# R205D.net
KiCad netlist of a schematic drawn in EAGLE
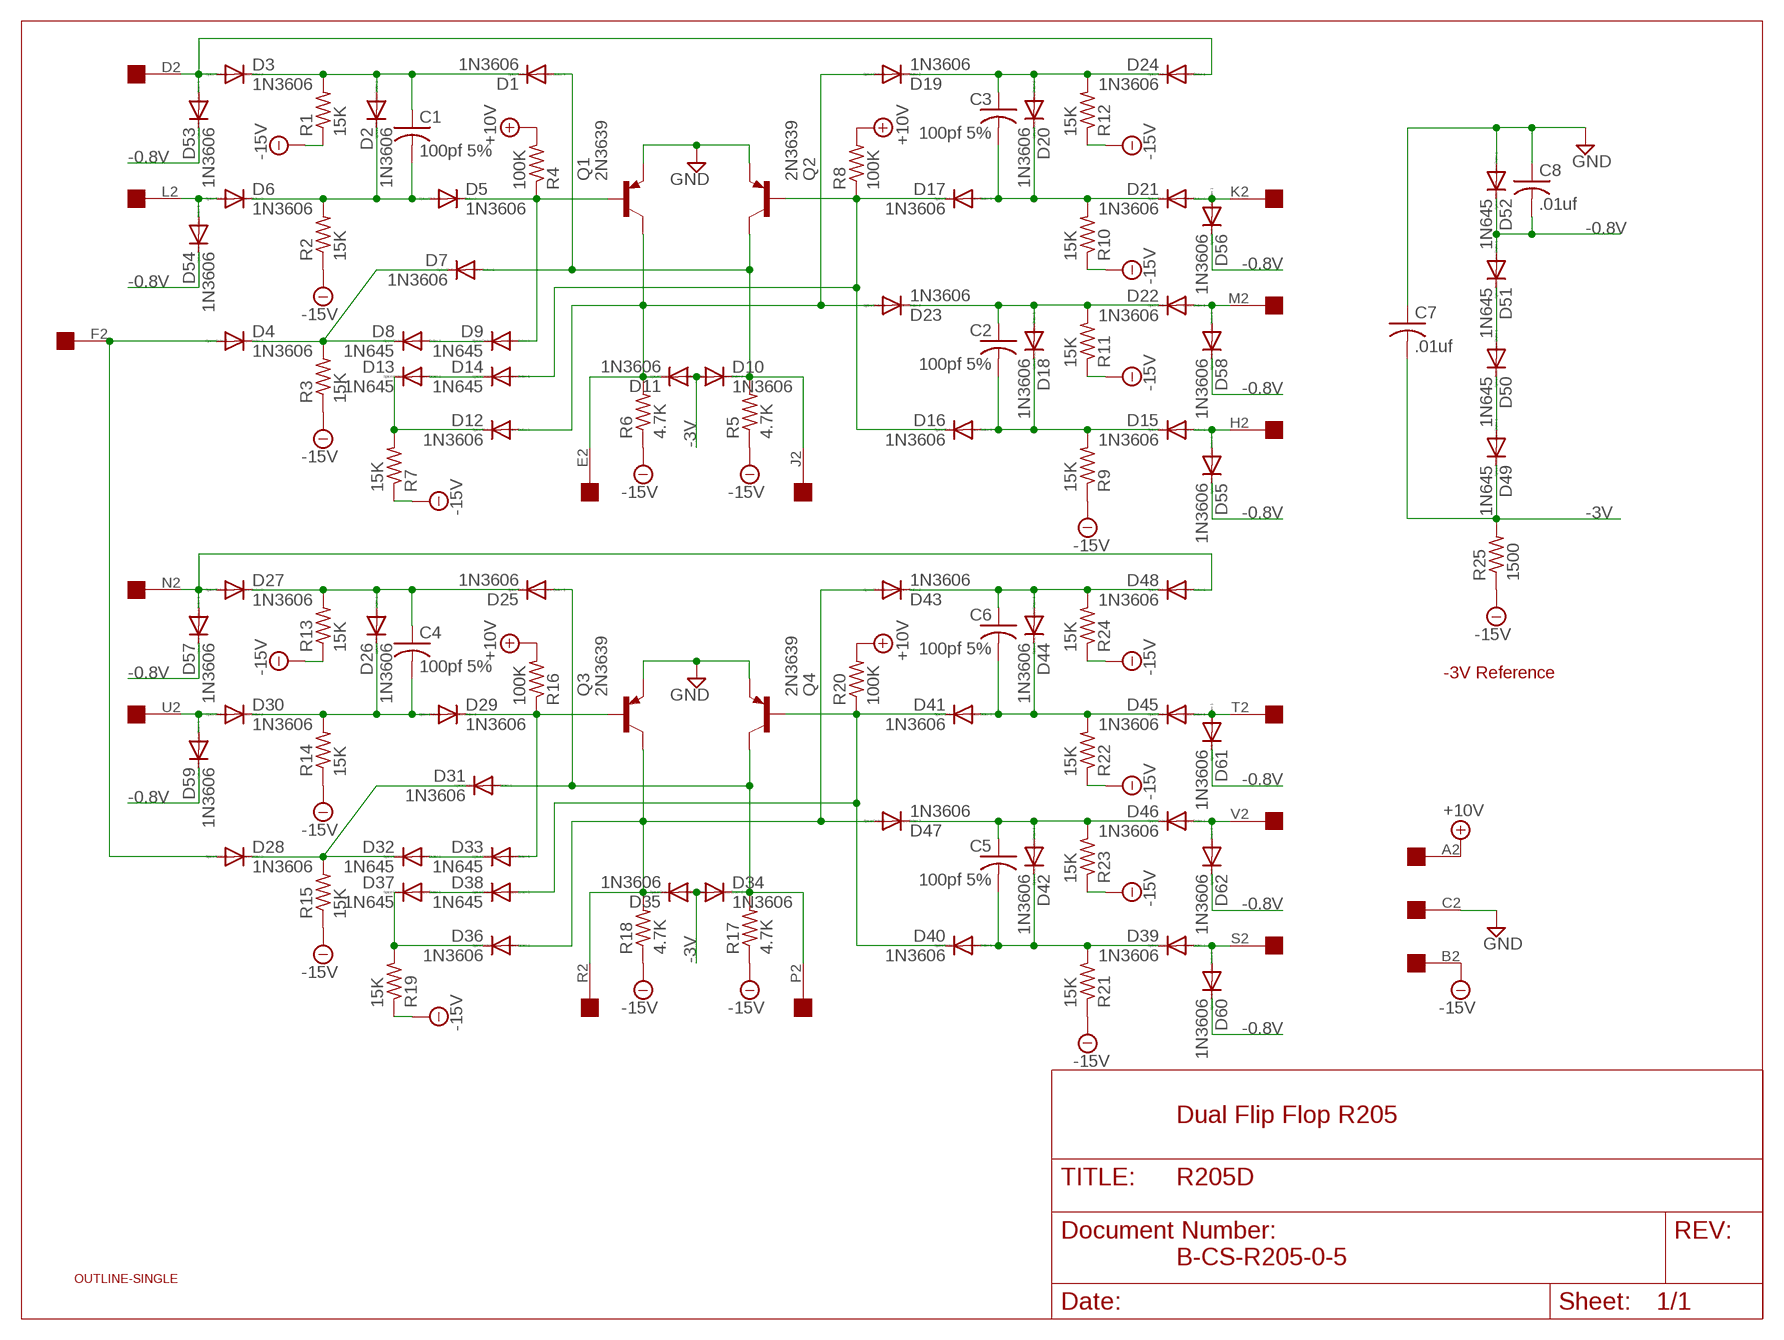
[diagram p0: schematic, sheet 1]

(export (version "E")
  (design (tool "Eeschema 10.0.6"))
  (components
    (comp (ref "C1")
      (value "100pf 5%")
      (footprint "eagle-import:C050-025X075")
      (libsource (lib "eagle-import") (part "C-US050-025X075"))
    )
    (comp (ref "C2")
      (value "100pf 5%")
      (footprint "eagle-import:C050-025X075")
      (libsource (lib "eagle-import") (part "C-US050-025X075"))
    )
    (comp (ref "C3")
      (value "100pf 5%")
      (footprint "eagle-import:C050-025X075")
      (libsource (lib "eagle-import") (part "C-US050-025X075"))
    )
    (comp (ref "C4")
      (value "100pf 5%")
      (footprint "eagle-import:C050-025X075")
      (libsource (lib "eagle-import") (part "C-US050-025X075"))
    )
    (comp (ref "C5")
      (value "100pf 5%")
      (footprint "eagle-import:C050-025X075")
      (libsource (lib "eagle-import") (part "C-US050-025X075"))
    )
    (comp (ref "C6")
      (value "100pf 5%")
      (footprint "eagle-import:C050-025X075")
      (libsource (lib "eagle-import") (part "C-US050-025X075"))
    )
    (comp (ref "C7")
      (value ".01uf")
      (footprint "eagle-import:C050-025X075")
      (libsource (lib "eagle-import") (part "C-US050-025X075"))
    )
    (comp (ref "C8")
      (value ".01uf")
      (footprint "eagle-import:C050-025X075")
      (libsource (lib "eagle-import") (part "C-US050-025X075"))
    )
    (comp (ref "D1")
      (value "1N3606")
      (footprint "eagle-import:DO35-10")
      (libsource (lib "eagle-import") (part "1N4148DO35-10"))
    )
    (comp (ref "D2")
      (value "1N3606")
      (footprint "eagle-import:DO35-10")
      (libsource (lib "eagle-import") (part "1N4148DO35-10"))
    )
    (comp (ref "D3")
      (value "1N3606")
      (footprint "eagle-import:DO35-10")
      (libsource (lib "eagle-import") (part "1N4148DO35-10"))
    )
    (comp (ref "D4")
      (value "1N3606")
      (footprint "eagle-import:DO35-10")
      (libsource (lib "eagle-import") (part "1N4148DO35-10"))
    )
    (comp (ref "D5")
      (value "1N3606")
      (footprint "eagle-import:DO35-10")
      (libsource (lib "eagle-import") (part "1N4148DO35-10"))
    )
    (comp (ref "D6")
      (value "1N3606")
      (footprint "eagle-import:DO35-10")
      (libsource (lib "eagle-import") (part "1N4148DO35-10"))
    )
    (comp (ref "D7")
      (value "1N3606")
      (footprint "eagle-import:DO35-10")
      (libsource (lib "eagle-import") (part "1N4148DO35-10"))
    )
    (comp (ref "D8")
      (value "1N645")
      (footprint "eagle-import:DO35-10")
      (libsource (lib "eagle-import") (part "1N4148DO35-10"))
    )
    (comp (ref "D9")
      (value "1N645")
      (footprint "eagle-import:DO35-10")
      (libsource (lib "eagle-import") (part "1N4148DO35-10"))
    )
    (comp (ref "D10")
      (value "1N3606")
      (footprint "eagle-import:DO35-10")
      (libsource (lib "eagle-import") (part "1N4148DO35-10"))
    )
    (comp (ref "D11")
      (value "1N3606")
      (footprint "eagle-import:DO35-10")
      (libsource (lib "eagle-import") (part "1N4148DO35-10"))
    )
    (comp (ref "D12")
      (value "1N3606")
      (footprint "eagle-import:DO35-10")
      (libsource (lib "eagle-import") (part "1N4148DO35-10"))
    )
    (comp (ref "D13")
      (value "1N645")
      (footprint "eagle-import:DO35-10")
      (libsource (lib "eagle-import") (part "1N4148DO35-10"))
    )
    (comp (ref "D14")
      (value "1N645")
      (footprint "eagle-import:DO35-10")
      (libsource (lib "eagle-import") (part "1N4148DO35-10"))
    )
    (comp (ref "D15")
      (value "1N3606")
      (footprint "eagle-import:DO35-10")
      (libsource (lib "eagle-import") (part "1N4148DO35-10"))
    )
    (comp (ref "D16")
      (value "1N3606")
      (footprint "eagle-import:DO35-10")
      (libsource (lib "eagle-import") (part "1N4148DO35-10"))
    )
    (comp (ref "D17")
      (value "1N3606")
      (footprint "eagle-import:DO35-10")
      (libsource (lib "eagle-import") (part "1N4148DO35-10"))
    )
    (comp (ref "D18")
      (value "1N3606")
      (footprint "eagle-import:DO35-10")
      (libsource (lib "eagle-import") (part "1N4148DO35-10"))
    )
    (comp (ref "D19")
      (value "1N3606")
      (footprint "eagle-import:DO35-10")
      (libsource (lib "eagle-import") (part "1N4148DO35-10"))
    )
    (comp (ref "D20")
      (value "1N3606")
      (footprint "eagle-import:DO35-10")
      (libsource (lib "eagle-import") (part "1N4148DO35-10"))
    )
    (comp (ref "D21")
      (value "1N3606")
      (footprint "eagle-import:DO35-10")
      (libsource (lib "eagle-import") (part "1N4148DO35-10"))
    )
    (comp (ref "D22")
      (value "1N3606")
      (footprint "eagle-import:DO35-10")
      (libsource (lib "eagle-import") (part "1N4148DO35-10"))
    )
    (comp (ref "D23")
      (value "1N3606")
      (footprint "eagle-import:DO35-10")
      (libsource (lib "eagle-import") (part "1N4148DO35-10"))
    )
    (comp (ref "D24")
      (value "1N3606")
      (footprint "eagle-import:DO35-10")
      (libsource (lib "eagle-import") (part "1N4148DO35-10"))
    )
    (comp (ref "D25")
      (value "1N3606")
      (footprint "eagle-import:DO35-10")
      (libsource (lib "eagle-import") (part "1N4148DO35-10"))
    )
    (comp (ref "D26")
      (value "1N3606")
      (footprint "eagle-import:DO35-10")
      (libsource (lib "eagle-import") (part "1N4148DO35-10"))
    )
    (comp (ref "D27")
      (value "1N3606")
      (footprint "eagle-import:DO35-10")
      (libsource (lib "eagle-import") (part "1N4148DO35-10"))
    )
    (comp (ref "D28")
      (value "1N3606")
      (footprint "eagle-import:DO35-10")
      (libsource (lib "eagle-import") (part "1N4148DO35-10"))
    )
    (comp (ref "D29")
      (value "1N3606")
      (footprint "eagle-import:DO35-10")
      (libsource (lib "eagle-import") (part "1N4148DO35-10"))
    )
    (comp (ref "D30")
      (value "1N3606")
      (footprint "eagle-import:DO35-10")
      (libsource (lib "eagle-import") (part "1N4148DO35-10"))
    )
    (comp (ref "D31")
      (value "1N3606")
      (footprint "eagle-import:DO35-10")
      (libsource (lib "eagle-import") (part "1N4148DO35-10"))
    )
    (comp (ref "D32")
      (value "1N645")
      (footprint "eagle-import:DO35-10")
      (libsource (lib "eagle-import") (part "1N4148DO35-10"))
    )
    (comp (ref "D33")
      (value "1N645")
      (footprint "eagle-import:DO35-10")
      (libsource (lib "eagle-import") (part "1N4148DO35-10"))
    )
    (comp (ref "D34")
      (value "1N3606")
      (footprint "eagle-import:DO35-10")
      (libsource (lib "eagle-import") (part "1N4148DO35-10"))
    )
    (comp (ref "D35")
      (value "1N3606")
      (footprint "eagle-import:DO35-10")
      (libsource (lib "eagle-import") (part "1N4148DO35-10"))
    )
    (comp (ref "D36")
      (value "1N3606")
      (footprint "eagle-import:DO35-10")
      (libsource (lib "eagle-import") (part "1N4148DO35-10"))
    )
    (comp (ref "D37")
      (value "1N645")
      (footprint "eagle-import:DO35-10")
      (libsource (lib "eagle-import") (part "1N4148DO35-10"))
    )
    (comp (ref "D38")
      (value "1N645")
      (footprint "eagle-import:DO35-10")
      (libsource (lib "eagle-import") (part "1N4148DO35-10"))
    )
    (comp (ref "D39")
      (value "1N3606")
      (footprint "eagle-import:DO35-10")
      (libsource (lib "eagle-import") (part "1N4148DO35-10"))
    )
    (comp (ref "D40")
      (value "1N3606")
      (footprint "eagle-import:DO35-10")
      (libsource (lib "eagle-import") (part "1N4148DO35-10"))
    )
    (comp (ref "D41")
      (value "1N3606")
      (footprint "eagle-import:DO35-10")
      (libsource (lib "eagle-import") (part "1N4148DO35-10"))
    )
    (comp (ref "D42")
      (value "1N3606")
      (footprint "eagle-import:DO35-10")
      (libsource (lib "eagle-import") (part "1N4148DO35-10"))
    )
    (comp (ref "D43")
      (value "1N3606")
      (footprint "eagle-import:DO35-10")
      (libsource (lib "eagle-import") (part "1N4148DO35-10"))
    )
    (comp (ref "D44")
      (value "1N3606")
      (footprint "eagle-import:DO35-10")
      (libsource (lib "eagle-import") (part "1N4148DO35-10"))
    )
    (comp (ref "D45")
      (value "1N3606")
      (footprint "eagle-import:DO35-10")
      (libsource (lib "eagle-import") (part "1N4148DO35-10"))
    )
    (comp (ref "D46")
      (value "1N3606")
      (footprint "eagle-import:DO35-10")
      (libsource (lib "eagle-import") (part "1N4148DO35-10"))
    )
    (comp (ref "D47")
      (value "1N3606")
      (footprint "eagle-import:DO35-10")
      (libsource (lib "eagle-import") (part "1N4148DO35-10"))
    )
    (comp (ref "D48")
      (value "1N3606")
      (footprint "eagle-import:DO35-10")
      (libsource (lib "eagle-import") (part "1N4148DO35-10"))
    )
    (comp (ref "D49")
      (value "1N645")
      (footprint "eagle-import:DO35-10")
      (libsource (lib "eagle-import") (part "1N4148DO35-10"))
    )
    (comp (ref "D50")
      (value "1N645")
      (footprint "eagle-import:DO35-10")
      (libsource (lib "eagle-import") (part "1N4148DO35-10"))
    )
    (comp (ref "D51")
      (value "1N645")
      (footprint "eagle-import:DO35-10")
      (libsource (lib "eagle-import") (part "1N4148DO35-10"))
    )
    (comp (ref "D52")
      (value "1N645")
      (footprint "eagle-import:DO35-10")
      (libsource (lib "eagle-import") (part "1N4148DO35-10"))
    )
    (comp (ref "D53")
      (value "1N3606")
      (footprint "eagle-import:DO35-10")
      (libsource (lib "eagle-import") (part "1N4148DO35-10"))
    )
    (comp (ref "D54")
      (value "1N3606")
      (footprint "eagle-import:DO35-10")
      (libsource (lib "eagle-import") (part "1N4148DO35-10"))
    )
    (comp (ref "D55")
      (value "1N3606")
      (footprint "eagle-import:DO35-10")
      (libsource (lib "eagle-import") (part "1N4148DO35-10"))
    )
    (comp (ref "D56")
      (value "1N3606")
      (footprint "eagle-import:DO35-10")
      (libsource (lib "eagle-import") (part "1N4148DO35-10"))
    )
    (comp (ref "D57")
      (value "1N3606")
      (footprint "eagle-import:DO35-10")
      (libsource (lib "eagle-import") (part "1N4148DO35-10"))
    )
    (comp (ref "D58")
      (value "1N3606")
      (footprint "eagle-import:DO35-10")
      (libsource (lib "eagle-import") (part "1N4148DO35-10"))
    )
    (comp (ref "D59")
      (value "1N3606")
      (footprint "eagle-import:DO35-10")
      (libsource (lib "eagle-import") (part "1N4148DO35-10"))
    )
    (comp (ref "D60")
      (value "1N3606")
      (footprint "eagle-import:DO35-10")
      (libsource (lib "eagle-import") (part "1N4148DO35-10"))
    )
    (comp (ref "D61")
      (value "1N3606")
      (footprint "eagle-import:DO35-10")
      (libsource (lib "eagle-import") (part "1N4148DO35-10"))
    )
    (comp (ref "D62")
      (value "1N3606")
      (footprint "eagle-import:DO35-10")
      (libsource (lib "eagle-import") (part "1N4148DO35-10"))
    )
    (comp (ref "Q1")
      (value "2N3639")
      (footprint "eagle-import:TO39")
      (libsource (lib "eagle-import") (part "2N3637"))
    )
    (comp (ref "Q2")
      (value "2N3639")
      (footprint "eagle-import:TO39")
      (libsource (lib "eagle-import") (part "2N3637"))
    )
    (comp (ref "Q3")
      (value "2N3639")
      (footprint "eagle-import:TO39")
      (libsource (lib "eagle-import") (part "2N3637"))
    )
    (comp (ref "Q4")
      (value "2N3639")
      (footprint "eagle-import:TO39")
      (libsource (lib "eagle-import") (part "2N3637"))
    )
    (comp (ref "R1")
      (value "15K")
      (footprint "eagle-import:0207_10")
      (libsource (lib "eagle-import") (part "R-US_0207/10"))
    )
    (comp (ref "R2")
      (value "15K")
      (footprint "eagle-import:0207_10")
      (libsource (lib "eagle-import") (part "R-US_0207/10"))
    )
    (comp (ref "R3")
      (value "15K")
      (footprint "eagle-import:0207_10")
      (libsource (lib "eagle-import") (part "R-US_0207/10"))
    )
    (comp (ref "R4")
      (value "100K")
      (footprint "eagle-import:0207_10")
      (libsource (lib "eagle-import") (part "R-US_0207/10"))
    )
    (comp (ref "R5")
      (value "4.7K")
      (footprint "eagle-import:0207_10")
      (libsource (lib "eagle-import") (part "R-US_0207/10"))
    )
    (comp (ref "R6")
      (value "4.7K")
      (footprint "eagle-import:0207_10")
      (libsource (lib "eagle-import") (part "R-US_0207/10"))
    )
    (comp (ref "R7")
      (value "15K")
      (footprint "eagle-import:0207_10")
      (libsource (lib "eagle-import") (part "R-US_0207/10"))
    )
    (comp (ref "R8")
      (value "100K")
      (footprint "eagle-import:0207_10")
      (libsource (lib "eagle-import") (part "R-US_0207/10"))
    )
    (comp (ref "R9")
      (value "15K")
      (footprint "eagle-import:0207_10")
      (libsource (lib "eagle-import") (part "R-US_0207/10"))
    )
    (comp (ref "R10")
      (value "15K")
      (footprint "eagle-import:0207_10")
      (libsource (lib "eagle-import") (part "R-US_0207/10"))
    )
    (comp (ref "R11")
      (value "15K")
      (footprint "eagle-import:0207_10")
      (libsource (lib "eagle-import") (part "R-US_0207/10"))
    )
    (comp (ref "R12")
      (value "15K")
      (footprint "eagle-import:0207_10")
      (libsource (lib "eagle-import") (part "R-US_0207/10"))
    )
    (comp (ref "R13")
      (value "15K")
      (footprint "eagle-import:0207_10")
      (libsource (lib "eagle-import") (part "R-US_0207/10"))
    )
    (comp (ref "R14")
      (value "15K")
      (footprint "eagle-import:0207_10")
      (libsource (lib "eagle-import") (part "R-US_0207/10"))
    )
    (comp (ref "R15")
      (value "15K")
      (footprint "eagle-import:0207_10")
      (libsource (lib "eagle-import") (part "R-US_0207/10"))
    )
    (comp (ref "R16")
      (value "100K")
      (footprint "eagle-import:0207_10")
      (libsource (lib "eagle-import") (part "R-US_0207/10"))
    )
    (comp (ref "R17")
      (value "4.7K")
      (footprint "eagle-import:0207_10")
      (libsource (lib "eagle-import") (part "R-US_0207/10"))
    )
    (comp (ref "R18")
      (value "4.7K")
      (footprint "eagle-import:0207_10")
      (libsource (lib "eagle-import") (part "R-US_0207/10"))
    )
    (comp (ref "R19")
      (value "15K")
      (footprint "eagle-import:0207_10")
      (libsource (lib "eagle-import") (part "R-US_0207/10"))
    )
    (comp (ref "R20")
      (value "100K")
      (footprint "eagle-import:0207_10")
      (libsource (lib "eagle-import") (part "R-US_0207/10"))
    )
    (comp (ref "R21")
      (value "15K")
      (footprint "eagle-import:0207_10")
      (libsource (lib "eagle-import") (part "R-US_0207/10"))
    )
    (comp (ref "R22")
      (value "15K")
      (footprint "eagle-import:0207_10")
      (libsource (lib "eagle-import") (part "R-US_0207/10"))
    )
    (comp (ref "R23")
      (value "15K")
      (footprint "eagle-import:0207_10")
      (libsource (lib "eagle-import") (part "R-US_0207/10"))
    )
    (comp (ref "R24")
      (value "15K")
      (footprint "eagle-import:0207_10")
      (libsource (lib "eagle-import") (part "R-US_0207/10"))
    )
    (comp (ref "R25")
      (value "1500")
      (footprint "eagle-import:0207_10")
      (libsource (lib "eagle-import") (part "R-US_0207/10"))
    )
    (comp (ref "U$1")
      (value "OUTLINE-SINGLE")
      (footprint "eagle-import:SINGLE")
      (libsource (lib "eagle-import") (part "OUTLINE-SINGLE"))
    )
    (comp (ref "U$2")
      (value "EDGE-1")
      (footprint "eagle-import:EDGE-CON1")
      (libsource (lib "eagle-import") (part "EDGE-1"))
    )
  )
  (nets
    (net (code "1") (name "+10V") (class "Default")
      (node (ref "R16") (pin "2") (pinfunction "2_2") (pintype "passive"))
      (node (ref "R20") (pin "2") (pinfunction "2_2") (pintype "passive"))
      (node (ref "R4") (pin "2") (pinfunction "2_2") (pintype "passive"))
      (node (ref "R8") (pin "2") (pinfunction "2_2") (pintype "passive"))
      (node (ref "U$2") (pin "A2") (pinfunction "1_A2") (pintype "bidirectional"))
    )
    (net (code "2") (name "-15V") (class "Default")
      (node (ref "R1") (pin "1") (pinfunction "1_1") (pintype "passive"))
      (node (ref "R10") (pin "1") (pinfunction "1_1") (pintype "passive"))
      (node (ref "R11") (pin "1") (pinfunction "1_1") (pintype "passive"))
      (node (ref "R12") (pin "1") (pinfunction "1_1") (pintype "passive"))
      (node (ref "R13") (pin "1") (pinfunction "1_1") (pintype "passive"))
      (node (ref "R14") (pin "1") (pinfunction "1_1") (pintype "passive"))
      (node (ref "R15") (pin "1") (pinfunction "1_1") (pintype "passive"))
      (node (ref "R17") (pin "1") (pinfunction "1_1") (pintype "passive"))
      (node (ref "R18") (pin "1") (pinfunction "1_1") (pintype "passive"))
      (node (ref "R19") (pin "1") (pinfunction "1_1") (pintype "passive"))
      (node (ref "R2") (pin "1") (pinfunction "1_1") (pintype "passive"))
      (node (ref "R21") (pin "1") (pinfunction "1_1") (pintype "passive"))
      (node (ref "R22") (pin "1") (pinfunction "1_1") (pintype "passive"))
      (node (ref "R23") (pin "1") (pinfunction "1_1") (pintype "passive"))
      (node (ref "R24") (pin "1") (pinfunction "1_1") (pintype "passive"))
      (node (ref "R25") (pin "1") (pinfunction "1_1") (pintype "passive"))
      (node (ref "R3") (pin "1") (pinfunction "1_1") (pintype "passive"))
      (node (ref "R5") (pin "1") (pinfunction "1_1") (pintype "passive"))
      (node (ref "R6") (pin "1") (pinfunction "1_1") (pintype "passive"))
      (node (ref "R7") (pin "1") (pinfunction "1_1") (pintype "passive"))
      (node (ref "R9") (pin "1") (pinfunction "1_1") (pintype "passive"))
      (node (ref "U$2") (pin "B2") (pinfunction "1_B2") (pintype "bidirectional"))
    )
    (net (code "3") (name "/-0.8V") (class "Default")
      (node (ref "C8") (pin "2") (pinfunction "2_2") (pintype "passive"))
      (node (ref "D51") (pin "A") (pinfunction "A_A") (pintype "passive"))
      (node (ref "D52") (pin "C") (pinfunction "C_C") (pintype "passive"))
      (node (ref "D53") (pin "C") (pinfunction "C_C") (pintype "passive"))
      (node (ref "D54") (pin "C") (pinfunction "C_C") (pintype "passive"))
      (node (ref "D55") (pin "C") (pinfunction "C_C") (pintype "passive"))
      (node (ref "D56") (pin "C") (pinfunction "C_C") (pintype "passive"))
      (node (ref "D57") (pin "C") (pinfunction "C_C") (pintype "passive"))
      (node (ref "D58") (pin "C") (pinfunction "C_C") (pintype "passive"))
      (node (ref "D59") (pin "C") (pinfunction "C_C") (pintype "passive"))
      (node (ref "D60") (pin "C") (pinfunction "C_C") (pintype "passive"))
      (node (ref "D61") (pin "C") (pinfunction "C_C") (pintype "passive"))
      (node (ref "D62") (pin "C") (pinfunction "C_C") (pintype "passive"))
    )
    (net (code "4") (name "/-3V") (class "Default")
      (node (ref "C7") (pin "2") (pinfunction "2_2") (pintype "passive"))
      (node (ref "D10") (pin "A") (pinfunction "A_A") (pintype "passive"))
      (node (ref "D11") (pin "A") (pinfunction "A_A") (pintype "passive"))
      (node (ref "D34") (pin "A") (pinfunction "A_A") (pintype "passive"))
      (node (ref "D35") (pin "A") (pinfunction "A_A") (pintype "passive"))
      (node (ref "D49") (pin "C") (pinfunction "C_C") (pintype "passive"))
      (node (ref "R25") (pin "2") (pinfunction "2_2") (pintype "passive"))
    )
    (net (code "5") (name "GND") (class "Default")
      (node (ref "C7") (pin "1") (pinfunction "1_1") (pintype "passive"))
      (node (ref "C8") (pin "1") (pinfunction "1_1") (pintype "passive"))
      (node (ref "D52") (pin "A") (pinfunction "A_A") (pintype "passive"))
      (node (ref "Q1") (pin "1") (pinfunction "E_1") (pintype "passive"))
      (node (ref "Q2") (pin "1") (pinfunction "E_1") (pintype "passive"))
      (node (ref "Q3") (pin "1") (pinfunction "E_1") (pintype "passive"))
      (node (ref "Q4") (pin "1") (pinfunction "E_1") (pintype "passive"))
      (node (ref "U$2") (pin "C2") (pinfunction "1_C2") (pintype "bidirectional"))
    )
    (net (code "6") (name "Net-(C1-Pad1)") (class "Default")
      (node (ref "C1") (pin "1") (pinfunction "1_1") (pintype "passive"))
      (node (ref "D1") (pin "C") (pinfunction "C_C") (pintype "passive"))
      (node (ref "D2") (pin "A") (pinfunction "A_A") (pintype "passive"))
      (node (ref "D3") (pin "C") (pinfunction "C_C") (pintype "passive"))
      (node (ref "R1") (pin "2") (pinfunction "2_2") (pintype "passive"))
    )
    (net (code "7") (name "Net-(C1-Pad2)") (class "Default")
      (node (ref "C1") (pin "2") (pinfunction "2_2") (pintype "passive"))
      (node (ref "D2") (pin "C") (pinfunction "C_C") (pintype "passive"))
      (node (ref "D5") (pin "A") (pinfunction "A_A") (pintype "passive"))
      (node (ref "D6") (pin "C") (pinfunction "C_C") (pintype "passive"))
      (node (ref "R2") (pin "2") (pinfunction "2_2") (pintype "passive"))
    )
    (net (code "8") (name "Net-(C2-Pad1)") (class "Default")
      (node (ref "C2") (pin "1") (pinfunction "1_1") (pintype "passive"))
      (node (ref "D18") (pin "A") (pinfunction "A_A") (pintype "passive"))
      (node (ref "D22") (pin "C") (pinfunction "C_C") (pintype "passive"))
      (node (ref "D23") (pin "C") (pinfunction "C_C") (pintype "passive"))
      (node (ref "R11") (pin "2") (pinfunction "2_2") (pintype "passive"))
    )
    (net (code "9") (name "Net-(C2-Pad2)") (class "Default")
      (node (ref "C2") (pin "2") (pinfunction "2_2") (pintype "passive"))
      (node (ref "D15") (pin "C") (pinfunction "C_C") (pintype "passive"))
      (node (ref "D16") (pin "A") (pinfunction "A_A") (pintype "passive"))
      (node (ref "D18") (pin "C") (pinfunction "C_C") (pintype "passive"))
      (node (ref "R9") (pin "2") (pinfunction "2_2") (pintype "passive"))
    )
    (net (code "10") (name "Net-(C3-Pad1)") (class "Default")
      (node (ref "C3") (pin "1") (pinfunction "1_1") (pintype "passive"))
      (node (ref "D19") (pin "C") (pinfunction "C_C") (pintype "passive"))
      (node (ref "D20") (pin "A") (pinfunction "A_A") (pintype "passive"))
      (node (ref "D24") (pin "C") (pinfunction "C_C") (pintype "passive"))
      (node (ref "R12") (pin "2") (pinfunction "2_2") (pintype "passive"))
    )
    (net (code "11") (name "Net-(C3-Pad2)") (class "Default")
      (node (ref "C3") (pin "2") (pinfunction "2_2") (pintype "passive"))
      (node (ref "D17") (pin "A") (pinfunction "A_A") (pintype "passive"))
      (node (ref "D20") (pin "C") (pinfunction "C_C") (pintype "passive"))
      (node (ref "D21") (pin "C") (pinfunction "C_C") (pintype "passive"))
      (node (ref "R10") (pin "2") (pinfunction "2_2") (pintype "passive"))
    )
    (net (code "12") (name "Net-(C4-Pad1)") (class "Default")
      (node (ref "C4") (pin "1") (pinfunction "1_1") (pintype "passive"))
      (node (ref "D25") (pin "C") (pinfunction "C_C") (pintype "passive"))
      (node (ref "D26") (pin "A") (pinfunction "A_A") (pintype "passive"))
      (node (ref "D27") (pin "C") (pinfunction "C_C") (pintype "passive"))
      (node (ref "R13") (pin "2") (pinfunction "2_2") (pintype "passive"))
    )
    (net (code "13") (name "Net-(C4-Pad2)") (class "Default")
      (node (ref "C4") (pin "2") (pinfunction "2_2") (pintype "passive"))
      (node (ref "D26") (pin "C") (pinfunction "C_C") (pintype "passive"))
      (node (ref "D29") (pin "A") (pinfunction "A_A") (pintype "passive"))
      (node (ref "D30") (pin "C") (pinfunction "C_C") (pintype "passive"))
      (node (ref "R14") (pin "2") (pinfunction "2_2") (pintype "passive"))
    )
    (net (code "14") (name "Net-(C5-Pad1)") (class "Default")
      (node (ref "C5") (pin "1") (pinfunction "1_1") (pintype "passive"))
      (node (ref "D42") (pin "A") (pinfunction "A_A") (pintype "passive"))
      (node (ref "D46") (pin "C") (pinfunction "C_C") (pintype "passive"))
      (node (ref "D47") (pin "C") (pinfunction "C_C") (pintype "passive"))
      (node (ref "R23") (pin "2") (pinfunction "2_2") (pintype "passive"))
    )
    (net (code "15") (name "Net-(C5-Pad2)") (class "Default")
      (node (ref "C5") (pin "2") (pinfunction "2_2") (pintype "passive"))
      (node (ref "D39") (pin "C") (pinfunction "C_C") (pintype "passive"))
      (node (ref "D40") (pin "A") (pinfunction "A_A") (pintype "passive"))
      (node (ref "D42") (pin "C") (pinfunction "C_C") (pintype "passive"))
      (node (ref "R21") (pin "2") (pinfunction "2_2") (pintype "passive"))
    )
    (net (code "16") (name "Net-(C6-Pad1)") (class "Default")
      (node (ref "C6") (pin "1") (pinfunction "1_1") (pintype "passive"))
      (node (ref "D43") (pin "C") (pinfunction "C_C") (pintype "passive"))
      (node (ref "D44") (pin "A") (pinfunction "A_A") (pintype "passive"))
      (node (ref "D48") (pin "C") (pinfunction "C_C") (pintype "passive"))
      (node (ref "R24") (pin "2") (pinfunction "2_2") (pintype "passive"))
    )
    (net (code "17") (name "Net-(C6-Pad2)") (class "Default")
      (node (ref "C6") (pin "2") (pinfunction "2_2") (pintype "passive"))
      (node (ref "D41") (pin "A") (pinfunction "A_A") (pintype "passive"))
      (node (ref "D44") (pin "C") (pinfunction "C_C") (pintype "passive"))
      (node (ref "D45") (pin "C") (pinfunction "C_C") (pintype "passive"))
      (node (ref "R22") (pin "2") (pinfunction "2_2") (pintype "passive"))
    )
    (net (code "18") (name "Net-(D4-PadC)") (class "Default")
      (node (ref "D4") (pin "C") (pinfunction "C_C") (pintype "passive"))
      (node (ref "D7") (pin "C") (pinfunction "C_C") (pintype "passive"))
      (node (ref "D8") (pin "C") (pinfunction "C_C") (pintype "passive"))
      (node (ref "R3") (pin "2") (pinfunction "2_2") (pintype "passive"))
    )
    (net (code "19") (name "Net-(D8-PadA)") (class "Default")
      (node (ref "D8") (pin "A") (pinfunction "A_A") (pintype "passive"))
      (node (ref "D9") (pin "C") (pinfunction "C_C") (pintype "passive"))
    )
    (net (code "20") (name "Net-(D12-PadC)") (class "Default")
      (node (ref "D12") (pin "C") (pinfunction "C_C") (pintype "passive"))
      (node (ref "D13") (pin "C") (pinfunction "C_C") (pintype "passive"))
      (node (ref "R7") (pin "2") (pinfunction "2_2") (pintype "passive"))
    )
    (net (code "21") (name "Net-(D13-PadA)") (class "Default")
      (node (ref "D13") (pin "A") (pinfunction "A_A") (pintype "passive"))
      (node (ref "D14") (pin "C") (pinfunction "C_C") (pintype "passive"))
    )
    (net (code "22") (name "Net-(D28-PadC)") (class "Default")
      (node (ref "D28") (pin "C") (pinfunction "C_C") (pintype "passive"))
      (node (ref "D31") (pin "C") (pinfunction "C_C") (pintype "passive"))
      (node (ref "D32") (pin "C") (pinfunction "C_C") (pintype "passive"))
      (node (ref "R15") (pin "2") (pinfunction "2_2") (pintype "passive"))
    )
    (net (code "23") (name "Net-(D32-PadA)") (class "Default")
      (node (ref "D32") (pin "A") (pinfunction "A_A") (pintype "passive"))
      (node (ref "D33") (pin "C") (pinfunction "C_C") (pintype "passive"))
    )
    (net (code "24") (name "Net-(D36-PadC)") (class "Default")
      (node (ref "D36") (pin "C") (pinfunction "C_C") (pintype "passive"))
      (node (ref "D37") (pin "C") (pinfunction "C_C") (pintype "passive"))
      (node (ref "R19") (pin "2") (pinfunction "2_2") (pintype "passive"))
    )
    (net (code "25") (name "Net-(D37-PadA)") (class "Default")
      (node (ref "D37") (pin "A") (pinfunction "A_A") (pintype "passive"))
      (node (ref "D38") (pin "C") (pinfunction "C_C") (pintype "passive"))
    )
    (net (code "26") (name "Net-(D49-PadA)") (class "Default")
      (node (ref "D49") (pin "A") (pinfunction "A_A") (pintype "passive"))
      (node (ref "D50") (pin "C") (pinfunction "C_C") (pintype "passive"))
    )
    (net (code "27") (name "Net-(D50-PadA)") (class "Default")
      (node (ref "D50") (pin "A") (pinfunction "A_A") (pintype "passive"))
      (node (ref "D51") (pin "C") (pinfunction "C_C") (pintype "passive"))
    )
    (net (code "28") (name "Net-(Q1-B)") (class "Default")
      (node (ref "D5") (pin "C") (pinfunction "C_C") (pintype "passive"))
      (node (ref "D9") (pin "A") (pinfunction "A_A") (pintype "passive"))
      (node (ref "Q1") (pin "2") (pinfunction "B_2") (pintype "passive"))
      (node (ref "R4") (pin "1") (pinfunction "1_1") (pintype "passive"))
    )
    (net (code "29") (name "Net-(Q1-C)") (class "Default")
      (node (ref "D11") (pin "C") (pinfunction "C_C") (pintype "passive"))
      (node (ref "D12") (pin "A") (pinfunction "A_A") (pintype "passive"))
      (node (ref "D19") (pin "A") (pinfunction "A_A") (pintype "passive"))
      (node (ref "D23") (pin "A") (pinfunction "A_A") (pintype "passive"))
      (node (ref "Q1") (pin "3") (pinfunction "C_3") (pintype "passive"))
      (node (ref "R6") (pin "2") (pinfunction "2_2") (pintype "passive"))
      (node (ref "U$2") (pin "E2") (pinfunction "1_E2") (pintype "bidirectional"))
    )
    (net (code "30") (name "Net-(Q2-B)") (class "Default")
      (node (ref "D14") (pin "A") (pinfunction "A_A") (pintype "passive"))
      (node (ref "D16") (pin "C") (pinfunction "C_C") (pintype "passive"))
      (node (ref "D17") (pin "C") (pinfunction "C_C") (pintype "passive"))
      (node (ref "Q2") (pin "2") (pinfunction "B_2") (pintype "passive"))
      (node (ref "R8") (pin "1") (pinfunction "1_1") (pintype "passive"))
    )
    (net (code "31") (name "Net-(Q2-C)") (class "Default")
      (node (ref "D1") (pin "A") (pinfunction "A_A") (pintype "passive"))
      (node (ref "D10") (pin "C") (pinfunction "C_C") (pintype "passive"))
      (node (ref "D7") (pin "A") (pinfunction "A_A") (pintype "passive"))
      (node (ref "Q2") (pin "3") (pinfunction "C_3") (pintype "passive"))
      (node (ref "R5") (pin "2") (pinfunction "2_2") (pintype "passive"))
      (node (ref "U$2") (pin "J2") (pinfunction "1_J2") (pintype "bidirectional"))
    )
    (net (code "32") (name "Net-(Q3-B)") (class "Default")
      (node (ref "D29") (pin "C") (pinfunction "C_C") (pintype "passive"))
      (node (ref "D33") (pin "A") (pinfunction "A_A") (pintype "passive"))
      (node (ref "Q3") (pin "2") (pinfunction "B_2") (pintype "passive"))
      (node (ref "R16") (pin "1") (pinfunction "1_1") (pintype "passive"))
    )
    (net (code "33") (name "Net-(Q3-C)") (class "Default")
      (node (ref "D35") (pin "C") (pinfunction "C_C") (pintype "passive"))
      (node (ref "D36") (pin "A") (pinfunction "A_A") (pintype "passive"))
      (node (ref "D43") (pin "A") (pinfunction "A_A") (pintype "passive"))
      (node (ref "D47") (pin "A") (pinfunction "A_A") (pintype "passive"))
      (node (ref "Q3") (pin "3") (pinfunction "C_3") (pintype "passive"))
      (node (ref "R18") (pin "2") (pinfunction "2_2") (pintype "passive"))
      (node (ref "U$2") (pin "R2") (pinfunction "1_R2") (pintype "bidirectional"))
    )
    (net (code "34") (name "Net-(Q4-B)") (class "Default")
      (node (ref "D38") (pin "A") (pinfunction "A_A") (pintype "passive"))
      (node (ref "D40") (pin "C") (pinfunction "C_C") (pintype "passive"))
      (node (ref "D41") (pin "C") (pinfunction "C_C") (pintype "passive"))
      (node (ref "Q4") (pin "2") (pinfunction "B_2") (pintype "passive"))
      (node (ref "R20") (pin "1") (pinfunction "1_1") (pintype "passive"))
    )
    (net (code "35") (name "Net-(Q4-C)") (class "Default")
      (node (ref "D25") (pin "A") (pinfunction "A_A") (pintype "passive"))
      (node (ref "D31") (pin "A") (pinfunction "A_A") (pintype "passive"))
      (node (ref "D34") (pin "C") (pinfunction "C_C") (pintype "passive"))
      (node (ref "Q4") (pin "3") (pinfunction "C_3") (pintype "passive"))
      (node (ref "R17") (pin "2") (pinfunction "2_2") (pintype "passive"))
      (node (ref "U$2") (pin "P2") (pinfunction "1_P2") (pintype "bidirectional"))
    )
    (net (code "36") (name "Net-(U$2D-1)") (class "Default")
      (node (ref "D24") (pin "A") (pinfunction "A_A") (pintype "passive"))
      (node (ref "D3") (pin "A") (pinfunction "A_A") (pintype "passive"))
      (node (ref "D53") (pin "A") (pinfunction "A_A") (pintype "passive"))
      (node (ref "U$2") (pin "D2") (pinfunction "1_D2") (pintype "bidirectional"))
    )
    (net (code "37") (name "Net-(U$2F-1)") (class "Default")
      (node (ref "D28") (pin "A") (pinfunction "A_A") (pintype "passive"))
      (node (ref "D4") (pin "A") (pinfunction "A_A") (pintype "passive"))
      (node (ref "U$2") (pin "F2") (pinfunction "1_F2") (pintype "bidirectional"))
    )
    (net (code "38") (name "Net-(U$2G-1)") (class "Default")
      (node (ref "D15") (pin "A") (pinfunction "A_A") (pintype "passive"))
      (node (ref "D55") (pin "A") (pinfunction "A_A") (pintype "passive"))
      (node (ref "U$2") (pin "H2") (pinfunction "1_H2") (pintype "bidirectional"))
    )
    (net (code "39") (name "Net-(U$2I-1)") (class "Default")
      (node (ref "D21") (pin "A") (pinfunction "A_A") (pintype "passive"))
      (node (ref "D56") (pin "A") (pinfunction "A_A") (pintype "passive"))
      (node (ref "U$2") (pin "K2") (pinfunction "1_K2") (pintype "bidirectional"))
    )
    (net (code "40") (name "Net-(U$2J-1)") (class "Default")
      (node (ref "D54") (pin "A") (pinfunction "A_A") (pintype "passive"))
      (node (ref "D6") (pin "A") (pinfunction "A_A") (pintype "passive"))
      (node (ref "U$2") (pin "L2") (pinfunction "1_L2") (pintype "bidirectional"))
    )
    (net (code "41") (name "Net-(U$2K-1)") (class "Default")
      (node (ref "D22") (pin "A") (pinfunction "A_A") (pintype "passive"))
      (node (ref "D58") (pin "A") (pinfunction "A_A") (pintype "passive"))
      (node (ref "U$2") (pin "M2") (pinfunction "1_M2") (pintype "bidirectional"))
    )
    (net (code "42") (name "Net-(U$2L-1)") (class "Default")
      (node (ref "D27") (pin "A") (pinfunction "A_A") (pintype "passive"))
      (node (ref "D48") (pin "A") (pinfunction "A_A") (pintype "passive"))
      (node (ref "D57") (pin "A") (pinfunction "A_A") (pintype "passive"))
      (node (ref "U$2") (pin "N2") (pinfunction "1_N2") (pintype "bidirectional"))
    )
    (net (code "43") (name "Net-(U$2O-1)") (class "Default")
      (node (ref "D39") (pin "A") (pinfunction "A_A") (pintype "passive"))
      (node (ref "D60") (pin "A") (pinfunction "A_A") (pintype "passive"))
      (node (ref "U$2") (pin "S2") (pinfunction "1_S2") (pintype "bidirectional"))
    )
    (net (code "44") (name "Net-(U$2P-1)") (class "Default")
      (node (ref "D45") (pin "A") (pinfunction "A_A") (pintype "passive"))
      (node (ref "D61") (pin "A") (pinfunction "A_A") (pintype "passive"))
      (node (ref "U$2") (pin "T2") (pinfunction "1_T2") (pintype "bidirectional"))
    )
    (net (code "45") (name "Net-(U$2Q-1)") (class "Default")
      (node (ref "D30") (pin "A") (pinfunction "A_A") (pintype "passive"))
      (node (ref "D59") (pin "A") (pinfunction "A_A") (pintype "passive"))
      (node (ref "U$2") (pin "U2") (pinfunction "1_U2") (pintype "bidirectional"))
    )
    (net (code "46") (name "Net-(U$2R-1)") (class "Default")
      (node (ref "D46") (pin "A") (pinfunction "A_A") (pintype "passive"))
      (node (ref "D62") (pin "A") (pinfunction "A_A") (pintype "passive"))
      (node (ref "U$2") (pin "V2") (pinfunction "1_V2") (pintype "bidirectional"))
    )
  )
)
